# IMU.net
KiCad netlist of a schematic drawn in Altium Designer
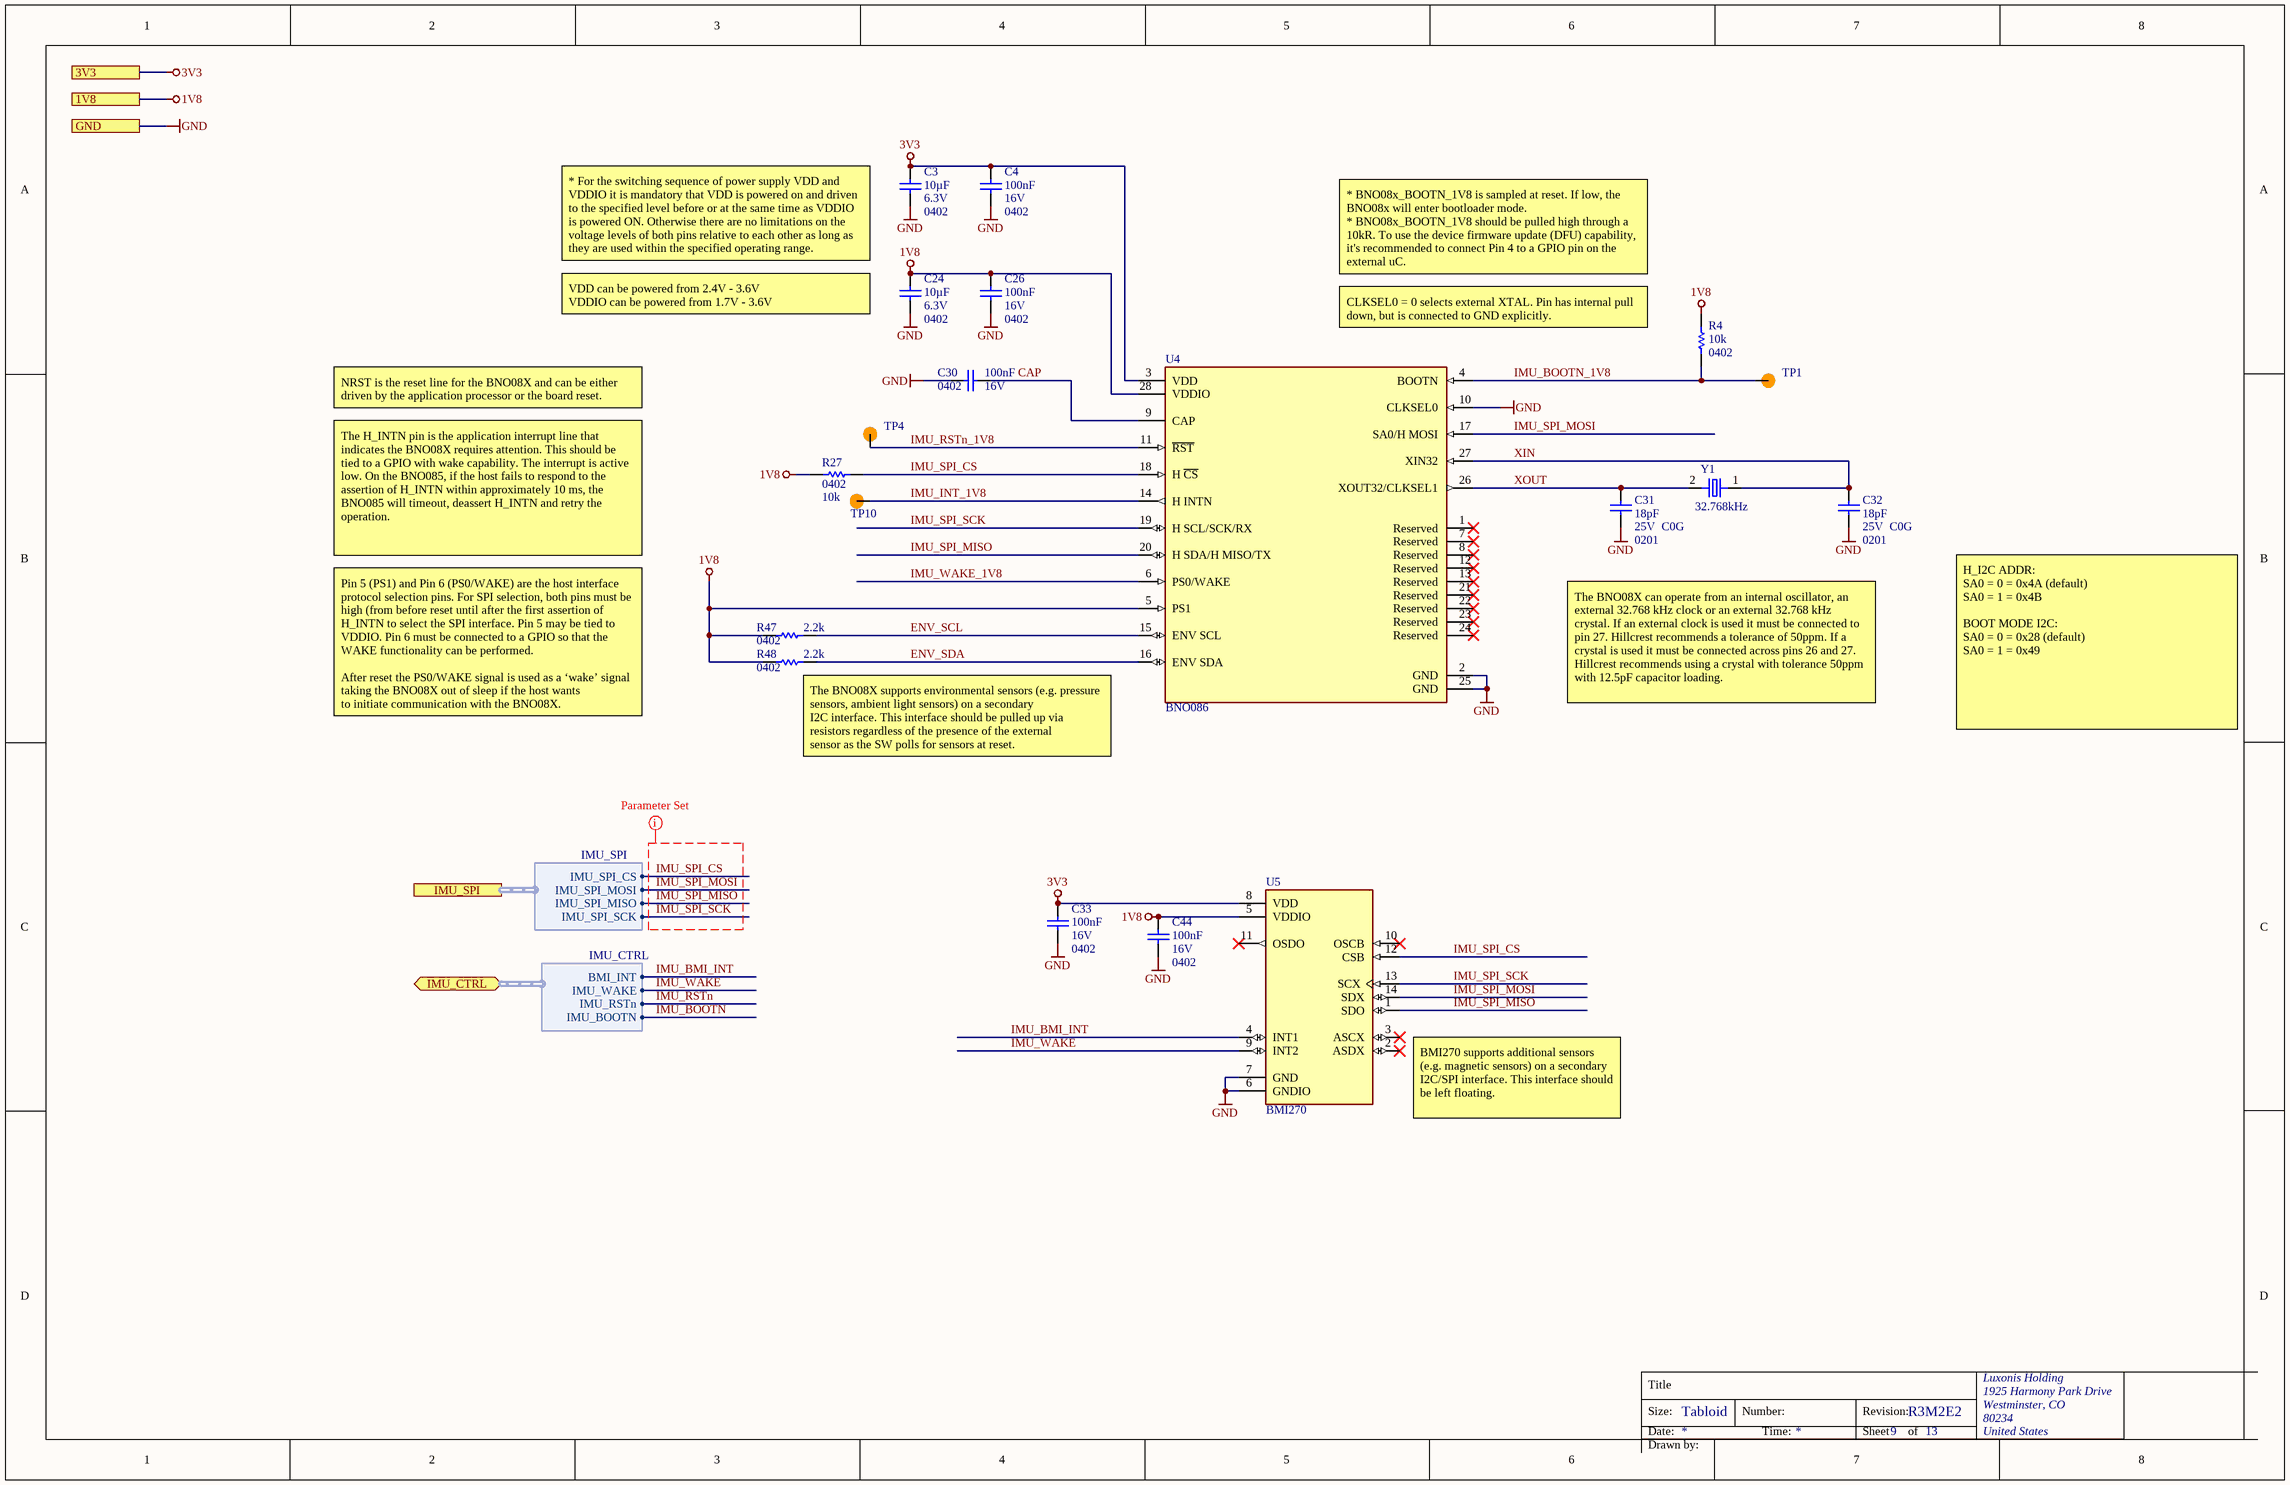
[diagram p0: IMU.SchDoc]

(export (version "E")
  (design (tool "Eeschema 10.0.6"))
  (components
    (comp (ref "C3")
      (value "10µF")
      (footprint "CAPC0402(1005)70_L")
      (description "CAP CER 10UF 6.3V X5R 0402 20%")
      (fields
        (field (name "VOLTAGE RATING") "6.3V")
        (field (name "CASE/PACKAGE") "0402")
        (field (name "TOLERANCE") "20%")
        (field (name "Comment") "GRM155R60J106ME15D")
      )
      (libsource (lib "Luxonis LLC") (part "LLL153C70G474ME17E"))
    )
    (comp (ref "C4")
      (value "100nF")
      (footprint "CAPC0402(1005)60_L")
      (description "CAP CER 0.1UF 16V X7R 0402 10%")
      (fields
        (field (name "VOLTAGE RATING") "16V")
        (field (name "CASE/PACKAGE") "0402")
        (field (name "TOLERANCE") "10%")
        (field (name "Comment") "CL05B104KO5NFNC")
      )
      (libsource (lib "Luxonis LLC") (part "GRM188R61C475KAAJD"))
    )
    (comp (ref "C24")
      (value "10µF")
      (footprint "CAPC0402(1005)70_L")
      (description "CAP CER 10UF 6.3V X5R 0402 20%")
      (fields
        (field (name "VOLTAGE RATING") "6.3V")
        (field (name "CASE/PACKAGE") "0402")
        (field (name "TOLERANCE") "20%")
        (field (name "Comment") "GRM155R60J106ME15D")
      )
      (libsource (lib "Luxonis LLC") (part "LLL153C70G474ME17E"))
    )
    (comp (ref "C26")
      (value "100nF")
      (footprint "CAPC0402(1005)60_L")
      (description "CAP CER 0.1UF 16V X7R 0402 10%")
      (fields
        (field (name "VOLTAGE RATING") "16V")
        (field (name "CASE/PACKAGE") "0402")
        (field (name "TOLERANCE") "10%")
        (field (name "Comment") "CL05B104KO5NFNC")
      )
      (libsource (lib "Luxonis LLC") (part "GRM188R61C475KAAJD"))
    )
    (comp (ref "C30")
      (value "100nF")
      (footprint "CAPC0402(1005)60_L")
      (description "CAP CER 0.1UF 16V X7R 0402 10%")
      (fields
        (field (name "VOLTAGE RATING") "16V")
        (field (name "CASE/PACKAGE") "0402")
        (field (name "TOLERANCE") "10%")
        (field (name "Comment") "CL05B104KO5NFNC")
      )
      (libsource (lib "Luxonis LLC") (part "GRM188R61C475KAAJD"))
    )
    (comp (ref "C31")
      (value "18pF")
      (footprint "CAPC0201(0603)33_L")
      (description "CAP CER 18PF 25V C0G 0201 10%")
      (fields
        (field (name "CASE/PACKAGE") "0201")
        (field (name "TOLERANCE") "1%")
        (field (name "VOLTAGE RATING") "25V")
        (field (name "DIELECTRIC") "C0G")
        (field (name "Comment") "GRM0335C1E180FA01D")
      )
      (libsource (lib "Luxonis LLC") (part "LLL153C70G474ME17E"))
    )
    (comp (ref "C32")
      (value "18pF")
      (footprint "CAPC0201(0603)33_L")
      (description "CAP CER 18PF 25V C0G 0201 10%")
      (fields
        (field (name "CASE/PACKAGE") "0201")
        (field (name "TOLERANCE") "1%")
        (field (name "VOLTAGE RATING") "25V")
        (field (name "DIELECTRIC") "C0G")
        (field (name "Comment") "GRM0335C1E180FA01D")
      )
      (libsource (lib "Luxonis LLC") (part "LLL153C70G474ME17E"))
    )
    (comp (ref "C33")
      (value "100nF")
      (footprint "CAPC0402(1005)60_L")
      (description "CAP CER 0.1UF 16V X7R 0402 10%")
      (fields
        (field (name "VOLTAGE RATING") "16V")
        (field (name "CASE/PACKAGE") "0402")
        (field (name "TOLERANCE") "10%")
        (field (name "Comment") "CL05B104KO5NFNC")
      )
      (libsource (lib "Luxonis LLC") (part "GRM188R61C475KAAJD"))
    )
    (comp (ref "C44")
      (value "100nF")
      (footprint "CAPC0402(1005)60_L")
      (description "CAP CER 0.1UF 16V X7R 0402 10%")
      (fields
        (field (name "VOLTAGE RATING") "16V")
        (field (name "CASE/PACKAGE") "0402")
        (field (name "TOLERANCE") "10%")
        (field (name "Comment") "CL05B104KO5NFNC")
      )
      (libsource (lib "Luxonis LLC") (part "GRM188R61C475KAAJD"))
    )
    (comp (ref "R4")
      (value "10k")
      (footprint "RESC0402(1005)_L")
      (description "RES SMD 10K OHM 1% 1/16W 0402")
      (fields
        (field (name "CASE/PACKAGE") "0402")
        (field (name "TOLERANCE") "1%")
        (field (name "Comment") "RC0402FR-1310KL")
      )
      (libsource (lib "Luxonis LLC") (part "RC0402FR-0722RL_1"))
    )
    (comp (ref "R27")
      (value "10k")
      (footprint "RESC0402(1005)_L")
      (description "RES SMD 10K OHM 1% 1/16W 0402")
      (fields
        (field (name "CASE/PACKAGE") "0402")
        (field (name "TOLERANCE") "1%")
        (field (name "Comment") "RC0402FR-1310KL")
      )
      (libsource (lib "Luxonis LLC") (part "RC0402FR-0722RL_1"))
    )
    (comp (ref "R47")
      (value "2.2k")
      (footprint "RESC0402(1005)_L")
      (description "RES SMD 2.2K OHM 1% 1/16W 0402")
      (fields
        (field (name "CASE/PACKAGE") "0402")
        (field (name "TOLERANCE") "1%")
        (field (name "Comment") "RC0402FR-072K2L")
      )
      (libsource (lib "Luxonis LLC") (part "Default resistor symbol"))
    )
    (comp (ref "R48")
      (value "2.2k")
      (footprint "RESC0402(1005)_L")
      (description "RES SMD 2.2K OHM 1% 1/16W 0402")
      (fields
        (field (name "CASE/PACKAGE") "0402")
        (field (name "TOLERANCE") "1%")
        (field (name "Comment") "RC0402FR-072K2L")
      )
      (libsource (lib "Luxonis LLC") (part "Default resistor symbol"))
    )
    (comp (ref "TP1")
      (value "TEST_POINT")
      (footprint "TP075_150_NS")
      (libsource (lib "Luxonis LLC") (part "TEST_POINT"))
    )
    (comp (ref "TP4")
      (value "TEST_POINT")
      (footprint "TP075_150_NS")
      (libsource (lib "Luxonis LLC") (part "TEST_POINT"))
    )
    (comp (ref "TP10")
      (value "TEST_POINT")
      (footprint "TP075_150_NS")
      (libsource (lib "Luxonis LLC") (part "TEST_POINT"))
    )
    (comp (ref "U4")
      (value "BNO086")
      (footprint "BNO086")
      (description "Accelerometer, Gyroscope, Magnetometer, 9 Axis Sensor I²C, SPI, UART Output")
      (libsource (lib "Luxonis LLC") (part "BNO086"))
    )
    (comp (ref "U5")
      (value "BMI270")
      (footprint "XDCR_BMI270")
      (description "Accelerometer, Gyroscope, 6 Axis Sensor IÂ²C, SPI Output")
      (libsource (lib "Luxonis LLC") (part "BMI270"))
    )
    (comp (ref "Y1")
      (value "ABS06-127-32.768KHZ-T")
      (footprint "ABS06-127-32.768KHZ-T")
      (description "CRYSTAL 32.768kHz ±20ppm Crystal 12.5pF 90 kOhms 2-SMD, No Lead")
      (fields (field (name "FREQUENCY") "32.768kHz") (field (name "TOLERANCE") "20ppm"))
      (libsource (lib "Luxonis LLC") (part "ABS06-127-32.768KHZ-T"))
    )
  )
  (nets
    (net (code "3") (name "/CAP") (class "Default")
      (node (ref "C30") (pin "1") (pinfunction "1_1") (pintype "passive"))
      (node (ref "U4") (pin "9") (pinfunction "CAP_9") (pintype "passive"))
    )
    (net (code "4") (name "/ENV_SCL") (class "Default")
      (node (ref "R47") (pin "2") (pinfunction "2_2") (pintype "passive"))
      (node (ref "U4") (pin "15") (pinfunction "ENV_SCL_15") (pintype "bidirectional"))
    )
    (net (code "5") (name "/ENV_SDA") (class "Default")
      (node (ref "R48") (pin "2") (pinfunction "2_2") (pintype "passive"))
      (node (ref "U4") (pin "16") (pinfunction "ENV_SDA_16") (pintype "bidirectional"))
    )
    (net (code "6") (name "/IMU_BMI_INT") (class "Default")
      (node (ref "U5") (pin "4") (pinfunction "INT1_4") (pintype "bidirectional"))
    )
    (net (code "8") (name "/IMU_BOOTN_1V8") (class "Default")
      (node (ref "R4") (pin "1") (pinfunction "1_1") (pintype "passive"))
      (node (ref "TP1") (pin "1") (pintype "passive"))
      (node (ref "U4") (pin "4") (pinfunction "BOOTN_4") (pintype "input"))
    )
    (net (code "9") (name "/IMU_INT_1V8") (class "Default")
      (node (ref "TP10") (pin "1") (pintype "passive"))
      (node (ref "U4") (pin "14") (pinfunction "H_INTN_14") (pintype "output"))
    )
    (net (code "11") (name "/IMU_RSTn_1V8") (class "Default")
      (node (ref "TP4") (pin "1") (pintype "passive"))
      (node (ref "U4") (pin "11") (pinfunction "~{RST}_11") (pintype "input"))
    )
    (net (code "12") (name "/IMU_SPI_CS") (class "Default")
      (node (ref "R27") (pin "1") (pinfunction "1_1") (pintype "passive"))
      (node (ref "U4") (pin "18") (pinfunction "H_~{CS}_18") (pintype "input"))
      (node (ref "U5") (pin "12") (pinfunction "CSB_12") (pintype "input"))
    )
    (net (code "13") (name "/IMU_SPI_MISO") (class "Default")
      (node (ref "U4") (pin "20") (pinfunction "H_SDA/H_MISO/TX_20") (pintype "bidirectional"))
      (node (ref "U5") (pin "1") (pinfunction "SDO_1") (pintype "bidirectional"))
    )
    (net (code "14") (name "/IMU_SPI_MOSI") (class "Default")
      (node (ref "U4") (pin "17") (pinfunction "SA0/H_MOSI_17") (pintype "input"))
      (node (ref "U5") (pin "14") (pinfunction "SDX_14") (pintype "bidirectional"))
    )
    (net (code "15") (name "/IMU_SPI_SCK") (class "Default")
      (node (ref "U4") (pin "19") (pinfunction "H_SCL/SCK/RX_19") (pintype "bidirectional"))
      (node (ref "U5") (pin "13") (pinfunction "SCX_13") (pintype "input"))
    )
    (net (code "16") (name "/IMU_WAKE") (class "Default")
      (node (ref "U5") (pin "9") (pinfunction "INT2_9") (pintype "bidirectional"))
    )
    (net (code "17") (name "/IMU_WAKE_1V8") (class "Default")
      (node (ref "U4") (pin "6") (pinfunction "PS0/WAKE_6") (pintype "input"))
    )
    (net (code "18") (name "/XIN") (class "Default")
      (node (ref "C32") (pin "2") (pinfunction "2_2") (pintype "passive"))
      (node (ref "U4") (pin "27") (pinfunction "XIN32_27") (pintype "input"))
      (node (ref "Y1") (pin "1") (pinfunction "1_1") (pintype "passive"))
    )
    (net (code "19") (name "/XOUT") (class "Default")
      (node (ref "C31") (pin "2") (pinfunction "2_2") (pintype "passive"))
      (node (ref "U4") (pin "26") (pinfunction "XOUT32/CLKSEL1_26") (pintype "output"))
      (node (ref "Y1") (pin "2") (pinfunction "2_2") (pintype "passive"))
    )
    (net (code "22") (name "1V8") (class "Default")
      (node (ref "C24") (pin "2") (pinfunction "2_2") (pintype "passive"))
      (node (ref "C26") (pin "2") (pinfunction "2_2") (pintype "passive"))
      (node (ref "C44") (pin "2") (pinfunction "2_2") (pintype "passive"))
      (node (ref "R27") (pin "2") (pinfunction "2_2") (pintype "passive"))
      (node (ref "R4") (pin "2") (pinfunction "2_2") (pintype "passive"))
      (node (ref "R47") (pin "1") (pinfunction "1_1") (pintype "passive"))
      (node (ref "R48") (pin "1") (pinfunction "1_1") (pintype "passive"))
      (node (ref "U4") (pin "28") (pinfunction "VDDIO_28") (pintype "power_in"))
      (node (ref "U4") (pin "5") (pinfunction "PS1_5") (pintype "input"))
      (node (ref "U5") (pin "5") (pinfunction "VDDIO_5") (pintype "power_in"))
    )
    (net (code "23") (name "3V3") (class "Default")
      (node (ref "C3") (pin "2") (pinfunction "2_2") (pintype "passive"))
      (node (ref "C33") (pin "2") (pinfunction "2_2") (pintype "passive"))
      (node (ref "C4") (pin "2") (pinfunction "2_2") (pintype "passive"))
      (node (ref "U4") (pin "3") (pinfunction "VDD_3") (pintype "power_in"))
      (node (ref "U5") (pin "8") (pinfunction "VDD_8") (pintype "power_in"))
    )
    (net (code "24") (name "GND") (class "Default")
      (node (ref "C24") (pin "1") (pinfunction "1_1") (pintype "passive"))
      (node (ref "C26") (pin "1") (pinfunction "1_1") (pintype "passive"))
      (node (ref "C3") (pin "1") (pinfunction "1_1") (pintype "passive"))
      (node (ref "C30") (pin "2") (pinfunction "2_2") (pintype "passive"))
      (node (ref "C31") (pin "1") (pinfunction "1_1") (pintype "passive"))
      (node (ref "C32") (pin "1") (pinfunction "1_1") (pintype "passive"))
      (node (ref "C33") (pin "1") (pinfunction "1_1") (pintype "passive"))
      (node (ref "C4") (pin "1") (pinfunction "1_1") (pintype "passive"))
      (node (ref "C44") (pin "1") (pinfunction "1_1") (pintype "passive"))
      (node (ref "U4") (pin "10") (pinfunction "CLKSEL0_10") (pintype "input"))
      (node (ref "U4") (pin "2") (pinfunction "GND_2") (pintype "power_in"))
      (node (ref "U4") (pin "25") (pinfunction "GND_25") (pintype "power_in"))
      (node (ref "U5") (pin "6") (pinfunction "GNDIO_6") (pintype "power_in"))
      (node (ref "U5") (pin "7") (pinfunction "GND_7") (pintype "power_in"))
    )
    (net (code "25") (name "unconnected-(U4-Reserved-Pad1)") (class "Default")
      (node (ref "U4") (pin "1") (pinfunction "Reserved_1") (pintype "passive+no_connect"))
    )
    (net (code "26") (name "unconnected-(U4-Reserved-Pad7)") (class "Default")
      (node (ref "U4") (pin "7") (pinfunction "Reserved_7") (pintype "passive+no_connect"))
    )
    (net (code "27") (name "unconnected-(U4-Reserved-Pad8)") (class "Default")
      (node (ref "U4") (pin "8") (pinfunction "Reserved_8") (pintype "passive+no_connect"))
    )
    (net (code "28") (name "unconnected-(U4-Reserved-Pad12)") (class "Default")
      (node (ref "U4") (pin "12") (pinfunction "Reserved_12") (pintype "passive+no_connect"))
    )
    (net (code "29") (name "unconnected-(U4-Reserved-Pad13)") (class "Default")
      (node (ref "U4") (pin "13") (pinfunction "Reserved_13") (pintype "passive+no_connect"))
    )
    (net (code "30") (name "unconnected-(U4-Reserved-Pad21)") (class "Default")
      (node (ref "U4") (pin "21") (pinfunction "Reserved_21") (pintype "passive+no_connect"))
    )
    (net (code "31") (name "unconnected-(U4-Reserved-Pad22)") (class "Default")
      (node (ref "U4") (pin "22") (pinfunction "Reserved_22") (pintype "passive+no_connect"))
    )
    (net (code "32") (name "unconnected-(U4-Reserved-Pad23)") (class "Default")
      (node (ref "U4") (pin "23") (pinfunction "Reserved_23") (pintype "passive+no_connect"))
    )
    (net (code "33") (name "unconnected-(U4-Reserved-Pad24)") (class "Default")
      (node (ref "U4") (pin "24") (pinfunction "Reserved_24") (pintype "passive+no_connect"))
    )
    (net (code "34") (name "unconnected-(U5-ASCX-Pad3)") (class "Default")
      (node (ref "U5") (pin "3") (pinfunction "ASCX_3") (pintype "bidirectional+no_connect"))
    )
    (net (code "35") (name "unconnected-(U5-ASDX-Pad2)") (class "Default")
      (node (ref "U5") (pin "2") (pinfunction "ASDX_2") (pintype "bidirectional+no_connect"))
    )
    (net (code "36") (name "unconnected-(U5-OSCB-Pad10)") (class "Default")
      (node (ref "U5") (pin "10") (pinfunction "OSCB_10") (pintype "input+no_connect"))
    )
    (net (code "37") (name "unconnected-(U5-OSDO-Pad11)") (class "Default")
      (node (ref "U5") (pin "11") (pinfunction "OSDO_11") (pintype "output+no_connect"))
    )
  )
)
